# pic_blk.net
KiCad netlist of a schematic drawn in Altium Designer
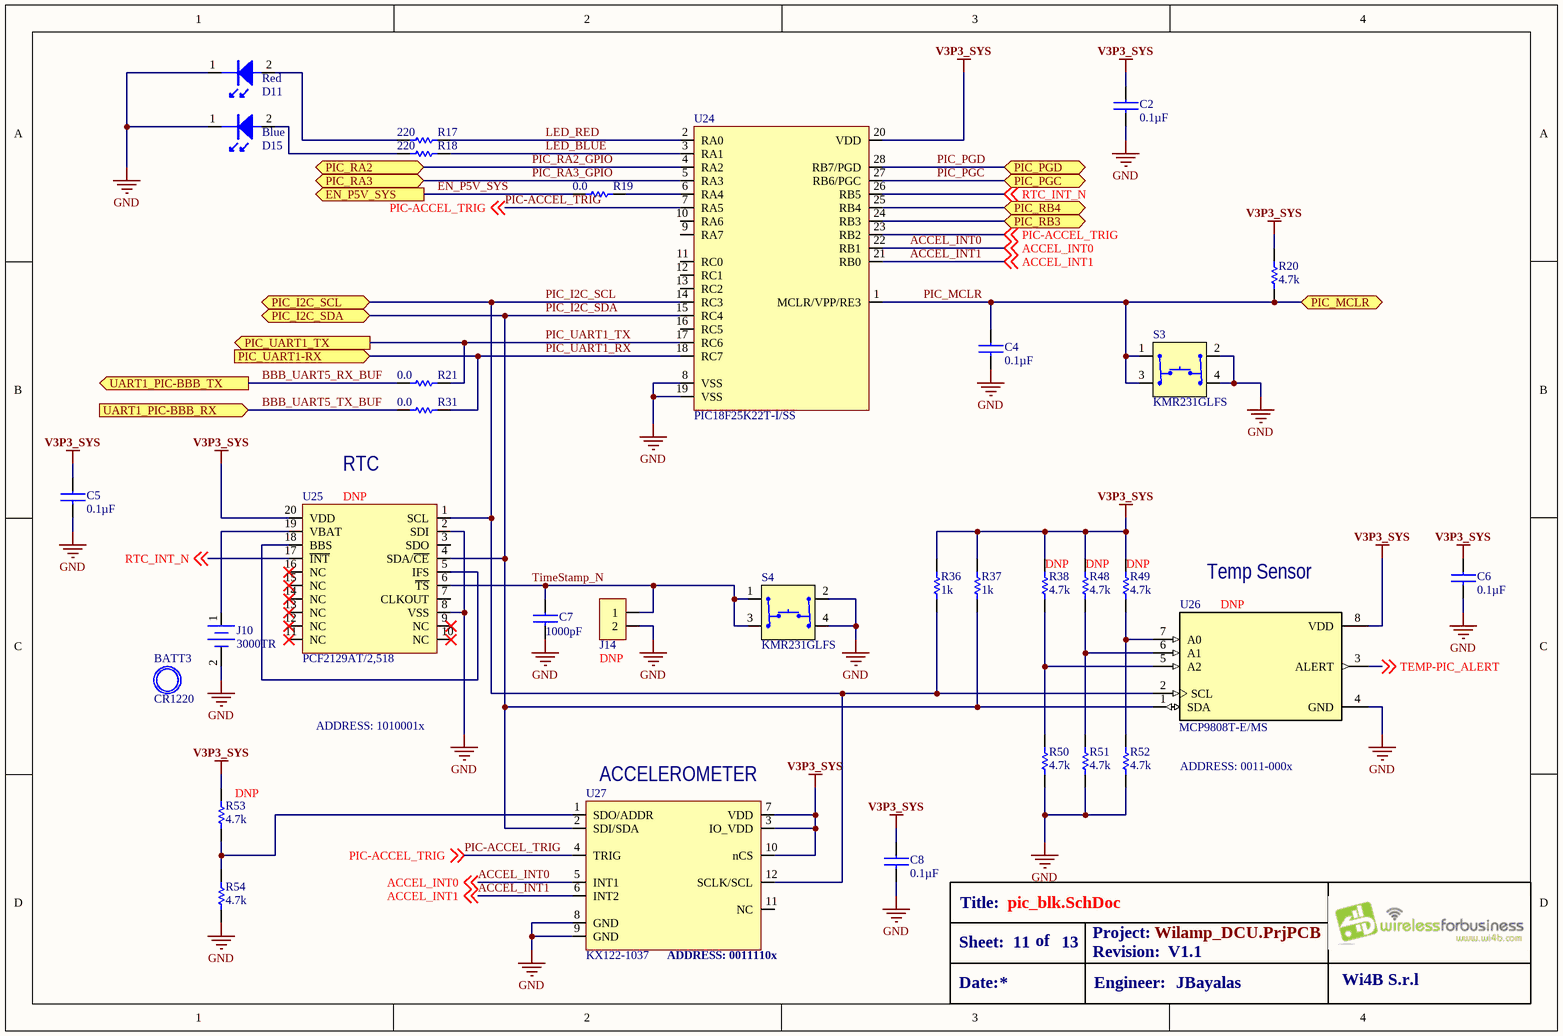
[diagram p0: pic_blk.SchDoc]

(export (version "E")
  (design (tool "Eeschema 10.0.6"))
  (components
    (comp (ref "BATT3")
      (value "CR1220")
      (description "Coin Cell Battery 35mAh 12.5mm")
      (fields (field (name "MPN") "CR1220"))
      (libsource (lib "Miscellaneous") (part "CR1220"))
    )
    (comp (ref "C2")
      (value "0.1µF")
      (footprint "C0402")
      (description "CAP CER 0.1UF 16V X7R 0402")
      (fields (field (name "MPN") "CL05B104KO3LNNC"))
      (libsource (lib "Capacitor") (part "CL05B104KO3LNNC"))
    )
    (comp (ref "C4")
      (value "0.1µF")
      (footprint "C0402")
      (description "CAP CER 0.1UF 16V X7R 0402")
      (fields (field (name "MPN") "CL05B104KO3LNNC"))
      (libsource (lib "Capacitor") (part "CL05B104KO3LNNC"))
    )
    (comp (ref "C5")
      (value "0.1µF")
      (footprint "C0402")
      (description "CAP CER 0.1UF 16V X7R 0402")
      (fields (field (name "MPN") "CL05B104KO3LNNC"))
      (libsource (lib "Capacitor") (part "CL05B104KO3LNNC"))
    )
    (comp (ref "C6")
      (value "0.1µF")
      (footprint "C0402")
      (description "CAP CER 0.1UF 16V X7R 0402")
      (fields (field (name "MPN") "CL05B104KO3LNNC"))
      (libsource (lib "Capacitor") (part "CL05B104KO3LNNC"))
    )
    (comp (ref "C7")
      (value "1000pF")
      (footprint "C0402")
      (description "CAP CER 1000PF 50V X7R 0402")
      (fields (field (name "MPN") "GRM155R71H102KA01D"))
      (libsource (lib "Capacitor") (part "GRM155R71H102KA01D"))
    )
    (comp (ref "C8")
      (value "0.1µF")
      (footprint "C0402")
      (description "CAP CER 0.1UF 16V X7R 0402")
      (fields (field (name "MPN") "CL05B104KO3LNNC"))
      (libsource (lib "Capacitor") (part "CL05B104KO3LNNC"))
    )
    (comp (ref "D11")
      (value "Red")
      (footprint "LED0402(RED)")
      (description "LED RED 0402 SMD")
      (fields (field (name "MPN") "LNJ247W82RA"))
      (libsource (lib "Diode") (part "LNJ247W82RA"))
    )
    (comp (ref "D15")
      (value "Blue")
      (footprint "LED0402(BLUE)")
      (description "LED BLUE 0402 SMD")
      (fields (field (name "MPN") "VLMB1500-GS08"))
      (libsource (lib "Diode") (part "VLMB1500-GS08"))
    )
    (comp (ref "J10")
      (value "3000TR")
      (footprint "3000TR")
      (description "Coin Cell Battery Holders SM COIN CELL B/H")
      (libsource (lib "Connector") (part "3000TR"))
    )
    (comp (ref "J14")
      (value "*")
      (footprint "2pin 5mm Pitch")
      (fields (field (name "LOAD") "DNP"))
      (libsource (lib "Miscellaneous") (part "2PIN Signal 5mm Pitch"))
    )
    (comp (ref "R17")
      (value "220")
      (footprint "R0402")
      (description "RES SMD 220 OHM 5% 1/16W 0402")
      (fields (field (name "MPN") "RC0402JR-07220RL"))
      (libsource (lib "Res") (part "RC0402JR-07220RL"))
    )
    (comp (ref "R18")
      (value "220")
      (footprint "R0402")
      (description "RES SMD 220 OHM 5% 1/16W 0402")
      (fields (field (name "MPN") "RC0402JR-07220RL"))
      (libsource (lib "Res") (part "RC0402JR-07220RL"))
    )
    (comp (ref "R19")
      (value "0.0")
      (footprint "R0402")
      (description "RES SMD 0.0OHM JUMPER 1/16W 0402")
      (fields (field (name "MPN") "CRCW04020000Z0ED"))
      (libsource (lib "Res") (part "CRCW04020000Z0ED"))
    )
    (comp (ref "R20")
      (value "4.7k")
      (footprint "R0603")
      (description "RES SMD 4.7K OHM 0.1% 1/10W 0603")
      (fields (field (name "MPN") "ERA-3AEB472V"))
      (libsource (lib "Res") (part "ERA-3AEB472V"))
    )
    (comp (ref "R21")
      (value "0.0")
      (footprint "R0402")
      (description "RES SMD 0.0OHM JUMPER 1/16W 0402")
      (fields (field (name "MPN") "CRCW04020000Z0ED"))
      (libsource (lib "Res") (part "CRCW04020000Z0ED"))
    )
    (comp (ref "R31")
      (value "0.0")
      (footprint "R0402")
      (description "RES SMD 0.0OHM JUMPER 1/16W 0402")
      (fields (field (name "MPN") "CRCW04020000Z0ED"))
      (libsource (lib "Res") (part "CRCW04020000Z0ED"))
    )
    (comp (ref "R36")
      (value "1k")
      (footprint "R0402")
      (description "RES SMD 1K OHM 1% 1/10W 0402")
      (fields (field (name "MPN") "MCS04020C1001FE000"))
      (libsource (lib "Res") (part "MCS04020C1001FE000"))
    )
    (comp (ref "R37")
      (value "1k")
      (footprint "R0402")
      (description "RES SMD 1K OHM 1% 1/10W 0402")
      (fields (field (name "MPN") "MCS04020C1001FE000"))
      (libsource (lib "Res") (part "MCS04020C1001FE000"))
    )
    (comp (ref "R38")
      (value "4.7k")
      (footprint "R0402")
      (description "RES SMD 4.7K OHM 5% 1/16W 0402")
      (fields (field (name "MPN") "RC0402JR-074K7L") (field (name "LOAD") "DNP"))
      (libsource (lib "Res") (part "RC0402JR-074K7L"))
    )
    (comp (ref "R48")
      (value "4.7k")
      (footprint "R0402")
      (description "RES SMD 4.7K OHM 5% 1/16W 0402")
      (fields (field (name "MPN") "RC0402JR-074K7L") (field (name "LOAD") "DNP"))
      (libsource (lib "Res") (part "RC0402JR-074K7L"))
    )
    (comp (ref "R49")
      (value "4.7k")
      (footprint "R0402")
      (description "RES SMD 4.7K OHM 5% 1/16W 0402")
      (fields (field (name "MPN") "RC0402JR-074K7L") (field (name "LOAD") "DNP"))
      (libsource (lib "Res") (part "RC0402JR-074K7L"))
    )
    (comp (ref "R50")
      (value "4.7k")
      (footprint "R0402")
      (description "RES SMD 4.7K OHM 5% 1/16W 0402")
      (fields (field (name "MPN") "RC0402JR-074K7L"))
      (libsource (lib "Res") (part "RC0402JR-074K7L"))
    )
    (comp (ref "R51")
      (value "4.7k")
      (footprint "R0402")
      (description "RES SMD 4.7K OHM 5% 1/16W 0402")
      (fields (field (name "MPN") "RC0402JR-074K7L"))
      (libsource (lib "Res") (part "RC0402JR-074K7L"))
    )
    (comp (ref "R52")
      (value "4.7k")
      (footprint "R0402")
      (description "RES SMD 4.7K OHM 5% 1/16W 0402")
      (fields (field (name "MPN") "RC0402JR-074K7L"))
      (libsource (lib "Res") (part "RC0402JR-074K7L"))
    )
    (comp (ref "R53")
      (value "4.7k")
      (footprint "R0402")
      (description "RES SMD 4.7K OHM 5% 1/16W 0402")
      (fields (field (name "MPN") "RC0402JR-074K7L") (field (name "LOAD") "DNP"))
      (libsource (lib "Res") (part "RC0402JR-074K7L"))
    )
    (comp (ref "R54")
      (value "4.7k")
      (footprint "R0402")
      (description "RES SMD 4.7K OHM 5% 1/16W 0402")
      (fields (field (name "MPN") "RC0402JR-074K7L"))
      (libsource (lib "Res") (part "RC0402JR-074K7L"))
    )
    (comp (ref "S3")
      (value "*")
      (footprint "KMR231G ULC LFS")
      (description "SWITCH TACTILE SPST-NO 0.05A 32V")
      (fields (field (name "MPN") "KMR231GLFS"))
      (libsource (lib "Switch") (part "KMR231GLFS"))
    )
    (comp (ref "S4")
      (value "*")
      (footprint "KMR231G ULC LFS")
      (description "SWITCH TACTILE SPST-NO 0.05A 32V")
      (fields (field (name "MPN") "KMR231GLFS"))
      (libsource (lib "Switch") (part "KMR231GLFS"))
    )
    (comp (ref "U24")
      (value "PIC18F25K22T-I/SS")
      (footprint "SSOP-28 (PIC)")
      (description "MCU 8BIT 32KB FLASH 28SSOP")
      (libsource (lib "IC") (part "PIC18F25K22T-I/SS"))
    )
    (comp (ref "U25")
      (value "PCF2129AT/2,518")
      (footprint "SOIC-20")
      (description "IC RTC /CALENDAR TCXO QTZ 20SOIC")
      (fields (field (name "LOAD") "DNP"))
      (libsource (lib "IC") (part "PCF2129AT/2,518"))
    )
    (comp (ref "U26")
      (value "MCP9808T-E/MS")
      (footprint "SOP65P490X110-8N")
      (description "MCP9808 Series 3.6 V Memory Module Digital Temperature Sensor SMT - MSOP-8")
      (fields (field (name "LOAD") "DNP"))
      (libsource (lib "SnapEDA") (part "MCP9808T-E/MS"))
    )
    (comp (ref "U27")
      (value "*")
      (footprint "KX122-1037")
      (description "ACCELEROMETER 2-8G I2C/SPI 12LGA")
      (fields (field (name "MPN") "KX122-1037"))
      (libsource (lib "IC") (part "KX122-1037"))
    )
  )
  (nets
    (net (code "1") (name "/BBB_UART5_RX_BUF") (class "Default")
      (node (ref "R21") (pin "2") (pinfunction "2_2") (pintype "passive"))
    )
    (net (code "2") (name "/BBB_UART5_TX_BUF") (class "Default")
      (node (ref "R31") (pin "2") (pinfunction "2_2") (pintype "passive"))
    )
    (net (code "3") (name "/EN_P5V_SYS") (class "Default")
      (node (ref "R19") (pin "2") (pinfunction "2_2") (pintype "passive"))
    )
    (net (code "4") (name "/LED_BLUE") (class "Default")
      (node (ref "R18") (pin "2") (pinfunction "2_2") (pintype "passive"))
      (node (ref "U24") (pin "3") (pinfunction "RA1_3") (pintype "passive"))
    )
    (net (code "5") (name "/LED_RED") (class "Default")
      (node (ref "R17") (pin "2") (pinfunction "2_2") (pintype "passive"))
      (node (ref "U24") (pin "2") (pinfunction "RA0_2") (pintype "passive"))
    )
    (net (code "6") (name "/PIC_I2C_SCL") (class "Default")
      (node (ref "R36") (pin "1") (pinfunction "1_1") (pintype "passive"))
      (node (ref "U24") (pin "14") (pinfunction "RC3_14") (pintype "passive"))
      (node (ref "U25") (pin "1") (pinfunction "SCL_1") (pintype "passive"))
      (node (ref "U26") (pin "2") (pinfunction "SCL_2") (pintype "input"))
      (node (ref "U27") (pin "12") (pinfunction "SCLK/SCL_12") (pintype "passive"))
    )
    (net (code "7") (name "/PIC_I2C_SDA") (class "Default")
      (node (ref "R37") (pin "1") (pinfunction "1_1") (pintype "passive"))
      (node (ref "U24") (pin "15") (pinfunction "RC4_15") (pintype "passive"))
      (node (ref "U25") (pin "4") (pinfunction "SDA/~{CE}_4") (pintype "passive"))
      (node (ref "U26") (pin "1") (pinfunction "SDA_1") (pintype "bidirectional"))
      (node (ref "U27") (pin "2") (pinfunction "SDI/SDA_2") (pintype "passive"))
    )
    (net (code "8") (name "/PIC_MCLR") (class "Default")
      (node (ref "C4") (pin "1") (pinfunction "1_1") (pintype "passive"))
      (node (ref "R20") (pin "1") (pinfunction "1_1") (pintype "passive"))
      (node (ref "S3") (pin "1") (pinfunction "1_1") (pintype "passive"))
      (node (ref "S3") (pin "3") (pinfunction "3_3") (pintype "passive"))
      (node (ref "U24") (pin "1") (pinfunction "MCLR/VPP/RE3_1") (pintype "passive"))
    )
    (net (code "9") (name "/PIC_PGC") (class "Default")
      (node (ref "U24") (pin "27") (pinfunction "RB6/PGC_27") (pintype "passive"))
    )
    (net (code "10") (name "/PIC_PGD") (class "Default")
      (node (ref "U24") (pin "28") (pinfunction "RB7/PGD_28") (pintype "passive"))
    )
    (net (code "11") (name "/PIC_RA2_GPIO") (class "Default")
      (node (ref "U24") (pin "4") (pinfunction "RA2_4") (pintype "passive"))
    )
    (net (code "12") (name "/PIC_RA3_GPIO") (class "Default")
      (node (ref "U24") (pin "5") (pinfunction "RA3_5") (pintype "passive"))
    )
    (net (code "13") (name "/PIC_RB3") (class "Default")
      (node (ref "U24") (pin "24") (pinfunction "RB3_24") (pintype "passive"))
    )
    (net (code "14") (name "/PIC_RB4") (class "Default")
      (node (ref "U24") (pin "25") (pinfunction "RB4_25") (pintype "passive"))
    )
    (net (code "15") (name "/PIC_UART1_RX") (class "Default")
      (node (ref "R31") (pin "1") (pinfunction "1_1") (pintype "passive"))
      (node (ref "U24") (pin "18") (pinfunction "RC7_18") (pintype "passive"))
    )
    (net (code "16") (name "/PIC_UART1_TX") (class "Default")
      (node (ref "R21") (pin "1") (pinfunction "1_1") (pintype "passive"))
      (node (ref "U24") (pin "17") (pinfunction "RC6_17") (pintype "passive"))
    )
    (net (code "17") (name "/TimeStamp_N") (class "Default")
      (node (ref "C7") (pin "1") (pinfunction "1_1") (pintype "passive"))
      (node (ref "J14") (pin "1") (pinfunction "1_1") (pintype "passive"))
      (node (ref "S4") (pin "1") (pinfunction "1_1") (pintype "passive"))
      (node (ref "S4") (pin "3") (pinfunction "3_3") (pintype "passive"))
      (node (ref "U25") (pin "6") (pinfunction "~{TS}_6") (pintype "passive"))
    )
    (net (code "18") (name "ACCEL_INT0") (class "Default")
      (node (ref "U24") (pin "22") (pinfunction "RB1_22") (pintype "passive"))
      (node (ref "U27") (pin "5") (pinfunction "INT1_5") (pintype "passive"))
    )
    (net (code "19") (name "ACCEL_INT1") (class "Default")
      (node (ref "U24") (pin "21") (pinfunction "RB0_21") (pintype "passive"))
      (node (ref "U27") (pin "6") (pinfunction "INT2_6") (pintype "passive"))
    )
    (net (code "20") (name "GND") (class "Default")
      (node (ref "C2") (pin "2") (pinfunction "2_2") (pintype "passive"))
      (node (ref "C4") (pin "2") (pinfunction "2_2") (pintype "passive"))
      (node (ref "C5") (pin "2") (pinfunction "2_2") (pintype "passive"))
      (node (ref "C6") (pin "2") (pinfunction "2_2") (pintype "passive"))
      (node (ref "C7") (pin "2") (pinfunction "2_2") (pintype "passive"))
      (node (ref "C8") (pin "2") (pinfunction "2_2") (pintype "passive"))
      (node (ref "D11") (pin "1") (pinfunction "1_1") (pintype "passive"))
      (node (ref "D15") (pin "1") (pinfunction "1_1") (pintype "passive"))
      (node (ref "J10") (pin "2") (pinfunction "-_2") (pintype "passive"))
      (node (ref "J14") (pin "2") (pinfunction "2_2") (pintype "passive"))
      (node (ref "R50") (pin "1") (pinfunction "1_1") (pintype "passive"))
      (node (ref "R51") (pin "1") (pinfunction "1_1") (pintype "passive"))
      (node (ref "R52") (pin "1") (pinfunction "1_1") (pintype "passive"))
      (node (ref "R54") (pin "1") (pinfunction "1_1") (pintype "passive"))
      (node (ref "S3") (pin "2") (pinfunction "2_2") (pintype "passive"))
      (node (ref "S3") (pin "4") (pinfunction "4_4") (pintype "passive"))
      (node (ref "S4") (pin "2") (pinfunction "2_2") (pintype "passive"))
      (node (ref "S4") (pin "4") (pinfunction "4_4") (pintype "passive"))
      (node (ref "U24") (pin "19") (pinfunction "VSS_19") (pintype "passive"))
      (node (ref "U24") (pin "8") (pinfunction "VSS_8") (pintype "passive"))
      (node (ref "U25") (pin "2") (pinfunction "SDI_2") (pintype "passive"))
      (node (ref "U25") (pin "8") (pinfunction "VSS_8") (pintype "passive"))
      (node (ref "U26") (pin "4") (pinfunction "GND_4") (pintype "power_in"))
      (node (ref "U27") (pin "8") (pinfunction "GND_8") (pintype "passive"))
      (node (ref "U27") (pin "9") (pinfunction "GND_9") (pintype "passive"))
    )
    (net (code "21") (name "Net-(D11-Pad2)") (class "Default")
      (node (ref "D11") (pin "2") (pinfunction "2_2") (pintype "passive"))
      (node (ref "R17") (pin "1") (pinfunction "1_1") (pintype "passive"))
    )
    (net (code "22") (name "Net-(D15-Pad2)") (class "Default")
      (node (ref "D15") (pin "2") (pinfunction "2_2") (pintype "passive"))
      (node (ref "R18") (pin "1") (pinfunction "1_1") (pintype "passive"))
    )
    (net (code "23") (name "Net-(J10-+)") (class "Default")
      (node (ref "J10") (pin "1") (pinfunction "+_1") (pintype "passive"))
      (node (ref "U25") (pin "19") (pinfunction "VBAT_19") (pintype "passive"))
    )
    (net (code "24") (name "Net-(U24-RA4)") (class "Default")
      (node (ref "R19") (pin "1") (pinfunction "1_1") (pintype "passive"))
      (node (ref "U24") (pin "6") (pinfunction "RA4_6") (pintype "passive"))
    )
    (net (code "25") (name "Net-(U25-BBS)") (class "Default")
      (node (ref "U25") (pin "18") (pinfunction "BBS_18") (pintype "passive"))
      (node (ref "U25") (pin "5") (pinfunction "IFS_5") (pintype "passive"))
    )
    (net (code "26") (name "Net-(U26-A0)") (class "Default")
      (node (ref "R49") (pin "1") (pinfunction "1_1") (pintype "passive"))
      (node (ref "R52") (pin "2") (pinfunction "2_2") (pintype "passive"))
      (node (ref "U26") (pin "7") (pinfunction "A0_7") (pintype "input"))
    )
    (net (code "27") (name "Net-(U26-A1)") (class "Default")
      (node (ref "R48") (pin "1") (pinfunction "1_1") (pintype "passive"))
      (node (ref "R51") (pin "2") (pinfunction "2_2") (pintype "passive"))
      (node (ref "U26") (pin "6") (pinfunction "A1_6") (pintype "input"))
    )
    (net (code "28") (name "Net-(U26-A2)") (class "Default")
      (node (ref "R38") (pin "1") (pinfunction "1_1") (pintype "passive"))
      (node (ref "R50") (pin "2") (pinfunction "2_2") (pintype "passive"))
      (node (ref "U26") (pin "5") (pinfunction "A2_5") (pintype "input"))
    )
    (net (code "29") (name "Net-(U27-SDO{slash}ADDR)") (class "Default")
      (node (ref "R53") (pin "1") (pinfunction "1_1") (pintype "passive"))
      (node (ref "R54") (pin "2") (pinfunction "2_2") (pintype "passive"))
      (node (ref "U27") (pin "1") (pinfunction "SDO/ADDR_1") (pintype "passive"))
    )
    (net (code "30") (name "PIC-ACCEL_TRIG") (class "Default")
      (node (ref "U24") (pin "23") (pinfunction "RB2_23") (pintype "passive"))
      (node (ref "U24") (pin "7") (pinfunction "RA5_7") (pintype "passive"))
      (node (ref "U27") (pin "4") (pinfunction "TRIG_4") (pintype "passive"))
    )
    (net (code "31") (name "RTC_INT_N") (class "Default")
      (node (ref "U24") (pin "26") (pinfunction "RB5_26") (pintype "passive"))
      (node (ref "U25") (pin "17") (pinfunction "~{INT}_17") (pintype "passive"))
    )
    (net (code "32") (name "TEMP-PIC_ALERT") (class "Default")
      (node (ref "U26") (pin "3") (pinfunction "ALERT_3") (pintype "output"))
    )
    (net (code "33") (name "V3P3_SYS") (class "Default")
      (node (ref "C2") (pin "1") (pinfunction "1_1") (pintype "passive"))
      (node (ref "C5") (pin "1") (pinfunction "1_1") (pintype "passive"))
      (node (ref "C6") (pin "1") (pinfunction "1_1") (pintype "passive"))
      (node (ref "C8") (pin "1") (pinfunction "1_1") (pintype "passive"))
      (node (ref "R20") (pin "2") (pinfunction "2_2") (pintype "passive"))
      (node (ref "R36") (pin "2") (pinfunction "2_2") (pintype "passive"))
      (node (ref "R37") (pin "2") (pinfunction "2_2") (pintype "passive"))
      (node (ref "R38") (pin "2") (pinfunction "2_2") (pintype "passive"))
      (node (ref "R48") (pin "2") (pinfunction "2_2") (pintype "passive"))
      (node (ref "R49") (pin "2") (pinfunction "2_2") (pintype "passive"))
      (node (ref "R53") (pin "2") (pinfunction "2_2") (pintype "passive"))
      (node (ref "U24") (pin "20") (pinfunction "VDD_20") (pintype "passive"))
      (node (ref "U25") (pin "20") (pinfunction "VDD_20") (pintype "passive"))
      (node (ref "U26") (pin "8") (pinfunction "VDD_8") (pintype "power_in"))
      (node (ref "U27") (pin "10") (pinfunction "nCS_10") (pintype "passive"))
      (node (ref "U27") (pin "3") (pinfunction "IO_VDD_3") (pintype "passive"))
      (node (ref "U27") (pin "7") (pinfunction "VDD_7") (pintype "passive"))
    )
    (net (code "34") (name "unconnected-(U24-RA6-Pad10)") (class "Default")
      (node (ref "U24") (pin "10") (pinfunction "RA6_10") (pintype "passive"))
    )
    (net (code "35") (name "unconnected-(U24-RA7-Pad9)") (class "Default")
      (node (ref "U24") (pin "9") (pinfunction "RA7_9") (pintype "passive"))
    )
    (net (code "36") (name "unconnected-(U24-RC0-Pad11)") (class "Default")
      (node (ref "U24") (pin "11") (pinfunction "RC0_11") (pintype "passive"))
    )
    (net (code "37") (name "unconnected-(U24-RC1-Pad12)") (class "Default")
      (node (ref "U24") (pin "12") (pinfunction "RC1_12") (pintype "passive"))
    )
    (net (code "38") (name "unconnected-(U24-RC2-Pad13)") (class "Default")
      (node (ref "U24") (pin "13") (pinfunction "RC2_13") (pintype "passive"))
    )
    (net (code "39") (name "unconnected-(U24-RC5-Pad16)") (class "Default")
      (node (ref "U24") (pin "16") (pinfunction "RC5_16") (pintype "passive"))
    )
    (net (code "40") (name "unconnected-(U25-CLKOUT-Pad7)") (class "Default")
      (node (ref "U25") (pin "7") (pinfunction "CLKOUT_7") (pintype "passive"))
    )
    (net (code "41") (name "unconnected-(U25-NC-Pad9)") (class "Default")
      (node (ref "U25") (pin "9") (pinfunction "NC_9") (pintype "passive+no_connect"))
    )
    (net (code "42") (name "unconnected-(U25-NC-Pad10)") (class "Default")
      (node (ref "U25") (pin "10") (pinfunction "NC_10") (pintype "passive+no_connect"))
    )
    (net (code "43") (name "unconnected-(U25-NC-Pad11)") (class "Default")
      (node (ref "U25") (pin "11") (pinfunction "NC_11") (pintype "passive+no_connect"))
    )
    (net (code "44") (name "unconnected-(U25-NC-Pad12)") (class "Default")
      (node (ref "U25") (pin "12") (pinfunction "NC_12") (pintype "passive+no_connect"))
    )
    (net (code "45") (name "unconnected-(U25-NC-Pad13)") (class "Default")
      (node (ref "U25") (pin "13") (pinfunction "NC_13") (pintype "passive+no_connect"))
    )
    (net (code "46") (name "unconnected-(U25-NC-Pad14)") (class "Default")
      (node (ref "U25") (pin "14") (pinfunction "NC_14") (pintype "passive+no_connect"))
    )
    (net (code "47") (name "unconnected-(U25-NC-Pad15)") (class "Default")
      (node (ref "U25") (pin "15") (pinfunction "NC_15") (pintype "passive+no_connect"))
    )
    (net (code "48") (name "unconnected-(U25-NC-Pad16)") (class "Default")
      (node (ref "U25") (pin "16") (pinfunction "NC_16") (pintype "passive+no_connect"))
    )
    (net (code "49") (name "unconnected-(U25-SDO-Pad3)") (class "Default")
      (node (ref "U25") (pin "3") (pinfunction "SDO_3") (pintype "passive"))
    )
    (net (code "50") (name "unconnected-(U27-NC-Pad11)") (class "Default")
      (node (ref "U27") (pin "11") (pinfunction "NC_11") (pintype "passive"))
    )
  )
)
